# board1.net
KiCad netlist of a schematic drawn in EAGLE
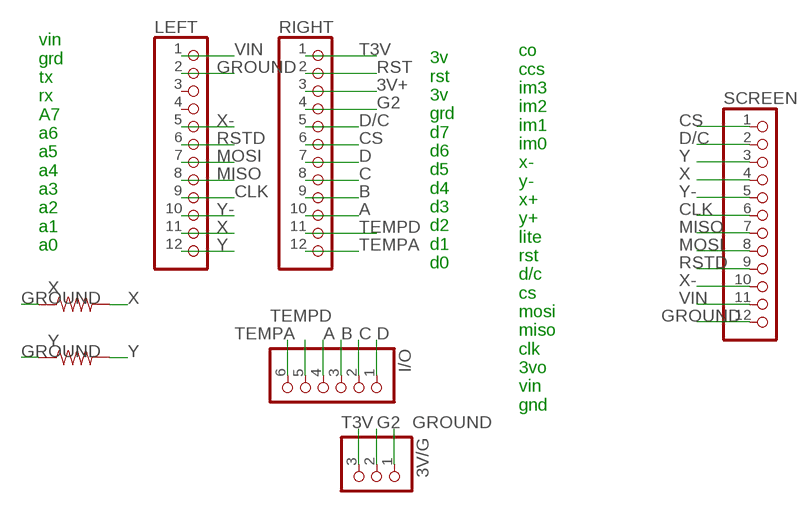
[diagram p0: schematic, sheet 1]

(export (version "E")
  (design (tool "Eeschema 10.0.6"))
  (components
    (comp (ref "3V/G")
      (value "PINHD-1X3CB")
      (footprint "eagle-import:1X03-CLEANBIG")
      (libsource (lib "eagle-import") (part "PINHD-1X3CB"))
    )
    (comp (ref "I/O")
      (value "PINHD-1X6CB")
      (footprint "eagle-import:1X06-CLEANBIG")
      (libsource (lib "eagle-import") (part "PINHD-1X6CB"))
    )
    (comp (ref "LEFT")
      (value "PINHD-1X12-CB")
      (footprint "eagle-import:1X12-CB")
      (libsource (lib "eagle-import") (part "PINHD-1X12-CB"))
    )
    (comp (ref "RIGHT")
      (value "PINHD-1X12-CB")
      (footprint "eagle-import:1X12-CB")
      (libsource (lib "eagle-import") (part "PINHD-1X12-CB"))
    )
    (comp (ref "SCREEN")
      (value "PINHD-1X12-CB")
      (footprint "eagle-import:1X12-CB")
      (libsource (lib "eagle-import") (part "PINHD-1X12-CB"))
    )
    (comp (ref "X")
      (value "10KOHM-1/6W-5%(PTH)KIT")
      (footprint "eagle-import:AXIAL-0.3-KIT")
      (libsource (lib "eagle-import") (part "10KOHM-1/6W-5%(PTH)KIT"))
    )
    (comp (ref "Y")
      (value "10KOHM-1/6W-5%(PTH)KIT")
      (footprint "eagle-import:AXIAL-0.3-KIT")
      (libsource (lib "eagle-import") (part "10KOHM-1/6W-5%(PTH)KIT"))
    )
  )
  (nets
    (net (code "1") (name "/3V+") (class "Default")
      (node (ref "RIGHT") (pin "3") (pinfunction "3_3") (pintype "passive"))
    )
    (net (code "2") (name "/A") (class "Default")
      (node (ref "I/O") (pin "4") (pinfunction "4_4") (pintype "passive"))
      (node (ref "RIGHT") (pin "10") (pinfunction "10_10") (pintype "passive"))
    )
    (net (code "3") (name "/B") (class "Default")
      (node (ref "I/O") (pin "3") (pinfunction "3_3") (pintype "passive"))
      (node (ref "RIGHT") (pin "9") (pinfunction "9_9") (pintype "passive"))
    )
    (net (code "4") (name "/C") (class "Default")
      (node (ref "I/O") (pin "2") (pinfunction "2_2") (pintype "passive"))
      (node (ref "RIGHT") (pin "8") (pinfunction "8_8") (pintype "passive"))
    )
    (net (code "5") (name "/CLK") (class "Default")
      (node (ref "LEFT") (pin "9") (pinfunction "9_9") (pintype "passive"))
      (node (ref "SCREEN") (pin "6") (pinfunction "6_6") (pintype "passive"))
    )
    (net (code "6") (name "/CS") (class "Default")
      (node (ref "RIGHT") (pin "6") (pinfunction "6_6") (pintype "passive"))
      (node (ref "SCREEN") (pin "1") (pinfunction "1_1") (pintype "passive"))
    )
    (net (code "7") (name "/D") (class "Default")
      (node (ref "I/O") (pin "1") (pinfunction "1_1") (pintype "passive"))
      (node (ref "RIGHT") (pin "7") (pinfunction "7_7") (pintype "passive"))
    )
    (net (code "8") (name "/D{slash}C") (class "Default")
      (node (ref "RIGHT") (pin "5") (pinfunction "5_5") (pintype "passive"))
      (node (ref "SCREEN") (pin "2") (pinfunction "2_2") (pintype "passive"))
    )
    (net (code "9") (name "/G2") (class "Default")
      (node (ref "3V/G") (pin "2") (pinfunction "2_2") (pintype "passive"))
      (node (ref "RIGHT") (pin "4") (pinfunction "4_4") (pintype "passive"))
    )
    (net (code "10") (name "/GROUND") (class "Default")
      (node (ref "3V/G") (pin "1") (pinfunction "1_1") (pintype "passive"))
      (node (ref "LEFT") (pin "2") (pinfunction "2_2") (pintype "passive"))
      (node (ref "SCREEN") (pin "12") (pinfunction "12_12") (pintype "passive"))
      (node (ref "X") (pin "P$1") (pinfunction "1_P$1") (pintype "passive"))
      (node (ref "Y") (pin "P$1") (pinfunction "1_P$1") (pintype "passive"))
    )
    (net (code "11") (name "/MISO") (class "Default")
      (node (ref "LEFT") (pin "8") (pinfunction "8_8") (pintype "passive"))
      (node (ref "SCREEN") (pin "7") (pinfunction "7_7") (pintype "passive"))
    )
    (net (code "12") (name "/MOSI") (class "Default")
      (node (ref "LEFT") (pin "7") (pinfunction "7_7") (pintype "passive"))
      (node (ref "SCREEN") (pin "8") (pinfunction "8_8") (pintype "passive"))
    )
    (net (code "13") (name "/RST") (class "Default")
      (node (ref "RIGHT") (pin "2") (pinfunction "2_2") (pintype "passive"))
    )
    (net (code "14") (name "/RSTD") (class "Default")
      (node (ref "LEFT") (pin "6") (pinfunction "6_6") (pintype "passive"))
      (node (ref "SCREEN") (pin "9") (pinfunction "9_9") (pintype "passive"))
    )
    (net (code "15") (name "/T3V") (class "Default")
      (node (ref "3V/G") (pin "3") (pinfunction "3_3") (pintype "passive"))
      (node (ref "RIGHT") (pin "1") (pinfunction "1_1") (pintype "passive"))
    )
    (net (code "16") (name "/TEMPA") (class "Default")
      (node (ref "I/O") (pin "6") (pinfunction "6_6") (pintype "passive"))
      (node (ref "RIGHT") (pin "12") (pinfunction "12_12") (pintype "passive"))
    )
    (net (code "17") (name "/TEMPD") (class "Default")
      (node (ref "I/O") (pin "5") (pinfunction "5_5") (pintype "passive"))
      (node (ref "RIGHT") (pin "11") (pinfunction "11_11") (pintype "passive"))
    )
    (net (code "18") (name "/VIN") (class "Default")
      (node (ref "LEFT") (pin "1") (pinfunction "1_1") (pintype "passive"))
      (node (ref "SCREEN") (pin "11") (pinfunction "11_11") (pintype "passive"))
    )
    (net (code "19") (name "/X") (class "Default")
      (node (ref "LEFT") (pin "11") (pinfunction "11_11") (pintype "passive"))
      (node (ref "SCREEN") (pin "4") (pinfunction "4_4") (pintype "passive"))
      (node (ref "X") (pin "P$2") (pinfunction "2_P$2") (pintype "passive"))
    )
    (net (code "20") (name "/X-") (class "Default")
      (node (ref "LEFT") (pin "5") (pinfunction "5_5") (pintype "passive"))
      (node (ref "SCREEN") (pin "10") (pinfunction "10_10") (pintype "passive"))
    )
    (net (code "21") (name "/Y") (class "Default")
      (node (ref "LEFT") (pin "12") (pinfunction "12_12") (pintype "passive"))
      (node (ref "SCREEN") (pin "3") (pinfunction "3_3") (pintype "passive"))
      (node (ref "Y") (pin "P$2") (pinfunction "2_P$2") (pintype "passive"))
    )
    (net (code "22") (name "/Y-") (class "Default")
      (node (ref "LEFT") (pin "10") (pinfunction "10_10") (pintype "passive"))
      (node (ref "SCREEN") (pin "5") (pinfunction "5_5") (pintype "passive"))
    )
    (net (code "23") (name "unconnected-(LEFT-Pad3)") (class "Default")
      (node (ref "LEFT") (pin "3") (pinfunction "3_3") (pintype "passive"))
    )
    (net (code "24") (name "unconnected-(LEFT-Pad4)") (class "Default")
      (node (ref "LEFT") (pin "4") (pinfunction "4_4") (pintype "passive"))
    )
  )
)
